# ProPrj___2025-02-25.net
KiCad netlist of a schematic drawn in EasyEDA Pro
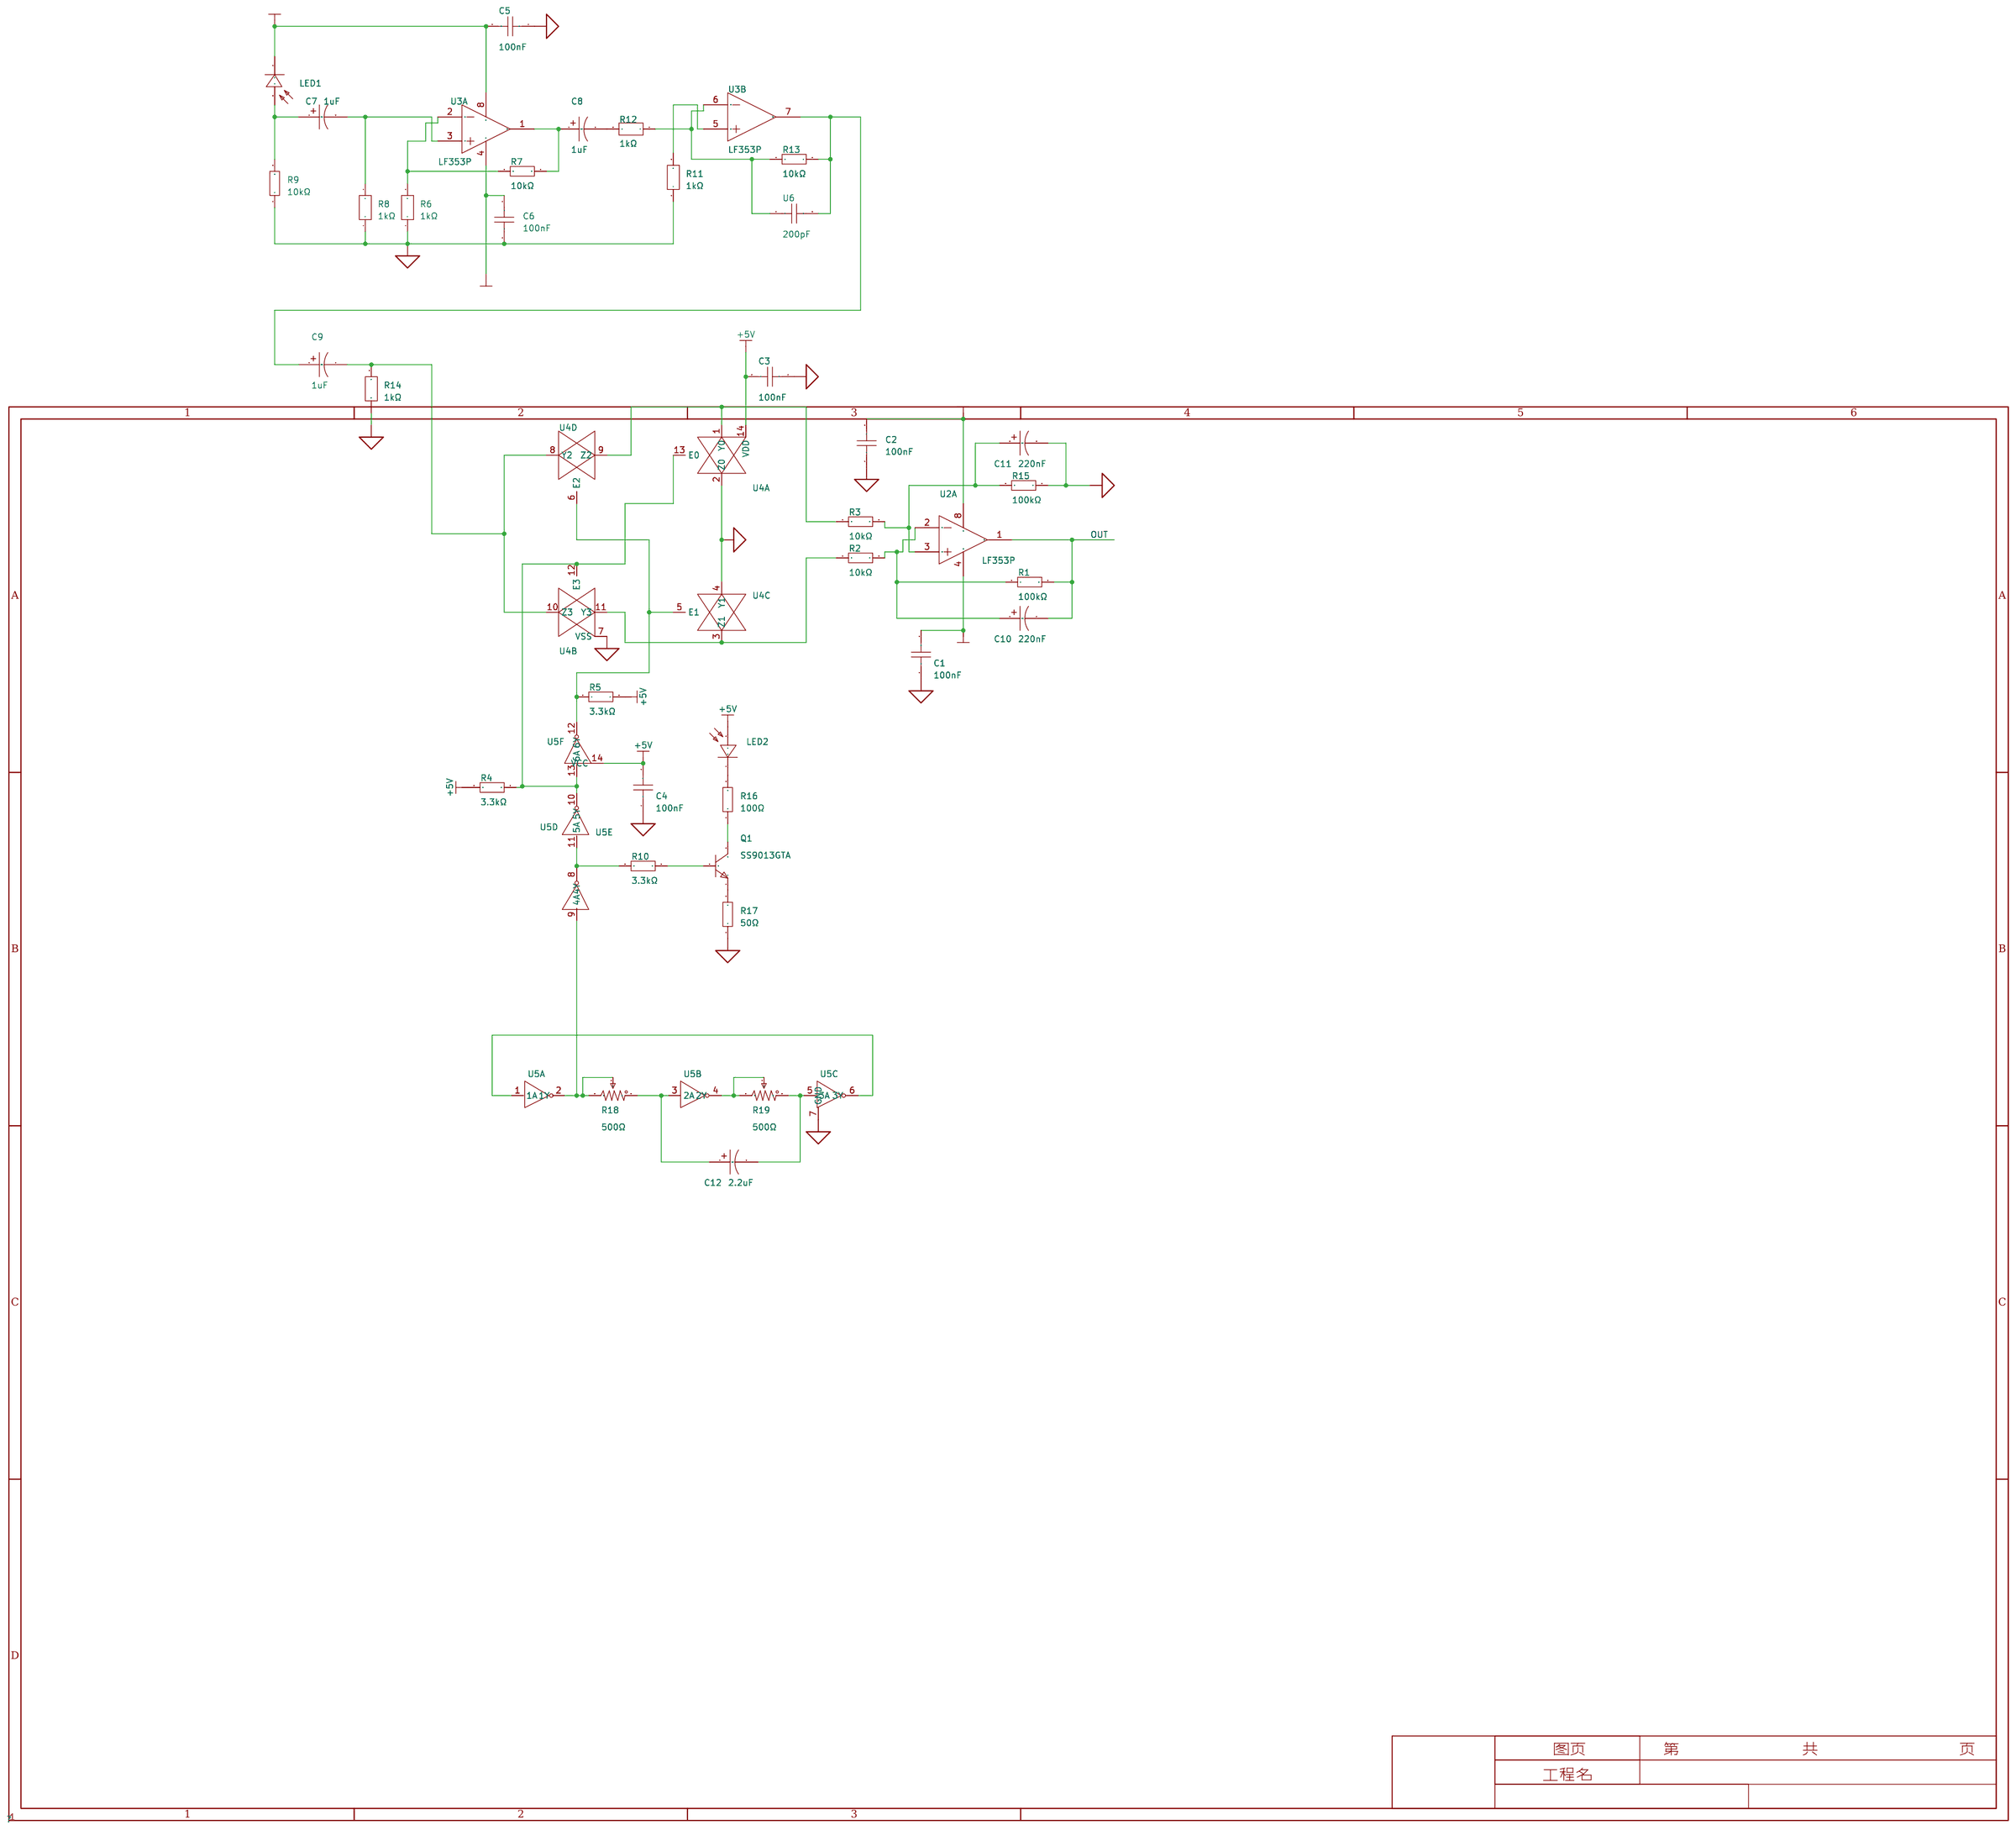
[diagram p0: schematic sheet]

(export (version "E")
  (design (tool "Eeschema 10.0.6"))
  (components
    (comp (ref "C1")
      (value "100nF")
      (footprint "easyedapro:C0402")
      (description "容值:100nF;精度:±10%;额定电压:50V;材质(温度系数):X7R;")
      (fields
        (field (name "Manufacturer Part") "GRM155R71H104KE14D")
        (field (name "Manufacturer") "muRata(村田)")
      )
      (libsource (lib "easyedapro") (part "GRM155R71H104KE14D"))
    )
    (comp (ref "C2")
      (value "100nF")
      (footprint "easyedapro:C0402")
      (description "容值:100nF;精度:±10%;额定电压:50V;材质(温度系数):X7R;")
      (fields
        (field (name "Manufacturer Part") "GRM155R71H104KE14D")
        (field (name "Manufacturer") "muRata(村田)")
      )
      (libsource (lib "easyedapro") (part "GRM155R71H104KE14D"))
    )
    (comp (ref "C3")
      (value "100nF")
      (footprint "easyedapro:C0402")
      (description "容值:100nF;精度:±10%;额定电压:50V;材质(温度系数):X7R;")
      (fields
        (field (name "Manufacturer Part") "GRM155R71H104KE14D")
        (field (name "Manufacturer") "muRata(村田)")
      )
      (libsource (lib "easyedapro") (part "GRM155R71H104KE14D"))
    )
    (comp (ref "C4")
      (value "100nF")
      (footprint "easyedapro:C0402")
      (description "容值:100nF;精度:±10%;额定电压:50V;材质(温度系数):X7R;")
      (fields
        (field (name "Manufacturer Part") "GRM155R71H104KE14D")
        (field (name "Manufacturer") "muRata(村田)")
      )
      (libsource (lib "easyedapro") (part "GRM155R71H104KE14D"))
    )
    (comp (ref "C5")
      (value "100nF")
      (footprint "easyedapro:C0402")
      (description "容值:100nF;精度:±10%;额定电压:50V;材质(温度系数):X7R;")
      (fields
        (field (name "Manufacturer Part") "GRM155R71H104KE14D")
        (field (name "Manufacturer") "muRata(村田)")
      )
      (libsource (lib "easyedapro") (part "GRM155R71H104KE14D"))
    )
    (comp (ref "C6")
      (value "100nF")
      (footprint "easyedapro:C0402")
      (description "容值:100nF;精度:±10%;额定电压:50V;材质(温度系数):X7R;")
      (fields
        (field (name "Manufacturer Part") "GRM155R71H104KE14D")
        (field (name "Manufacturer") "muRata(村田)")
      )
      (libsource (lib "easyedapro") (part "GRM155R71H104KE14D"))
    )
    (comp (ref "C7")
      (value "1uF")
      (footprint "easyedapro:CAP-TH_BD5.0-P2.00-D0.5-FD-1")
      (description "容值:1uF;精度:±20%;额定电压:50V;纹波电流:-;等效串联电阻:-;")
      (fields
        (field (name "Manufacturer Part") "50YXF1MEFC5X11")
        (field (name "Manufacturer") "rubycon(红宝石)")
      )
      (libsource (lib "easyedapro") (part "50YXF1MEFC5X11_C2927584"))
    )
    (comp (ref "C8")
      (value "1uF")
      (footprint "easyedapro:CAP-TH_BD5.0-P2.00-D0.5-FD-1")
      (description "容值:1uF;精度:±20%;额定电压:50V;纹波电流:-;等效串联电阻:-;")
      (fields
        (field (name "Manufacturer Part") "50YXF1MEFC5X11")
        (field (name "Manufacturer") "rubycon(红宝石)")
      )
      (libsource (lib "easyedapro") (part "50YXF1MEFC5X11_C2927584"))
    )
    (comp (ref "C9")
      (value "1uF")
      (footprint "easyedapro:CAP-TH_BD5.0-P2.00-D0.5-FD-1")
      (description "容值:1uF;精度:±20%;额定电压:50V;纹波电流:-;等效串联电阻:-;")
      (fields
        (field (name "Manufacturer Part") "50YXF1MEFC5X11")
        (field (name "Manufacturer") "rubycon(红宝石)")
      )
      (libsource (lib "easyedapro") (part "50YXF1MEFC5X11_C2927584"))
    )
    (comp (ref "C10")
      (value "220nF")
      (footprint "easyedapro:CAP-TH_BD5.0-P2.00-D0.5-FD-1")
      (description "容值:1uF;精度:±20%;额定电压:50V;纹波电流:-;等效串联电阻:-;")
      (fields
        (field (name "Manufacturer Part") "50YXF1MEFC5X11")
        (field (name "Manufacturer") "rubycon(红宝石)")
      )
      (libsource (lib "easyedapro") (part "50YXF1MEFC5X11_C2927584"))
    )
    (comp (ref "C11")
      (value "220nF")
      (footprint "easyedapro:CAP-TH_BD5.0-P2.00-D0.5-FD-1")
      (description "容值:1uF;精度:±20%;额定电压:50V;纹波电流:-;等效串联电阻:-;")
      (fields
        (field (name "Manufacturer Part") "50YXF1MEFC5X11")
        (field (name "Manufacturer") "rubycon(红宝石)")
      )
      (libsource (lib "easyedapro") (part "50YXF1MEFC5X11_C2927584"))
    )
    (comp (ref "C12")
      (value "2.2uF")
      (footprint "easyedapro:CAP-TH_BD5.0-P2.00-D0.5-FD-1")
      (description "容值:1uF;精度:±20%;额定电压:50V;纹波电流:-;等效串联电阻:-;")
      (fields
        (field (name "Manufacturer Part") "50YXF1MEFC5X11")
        (field (name "Manufacturer") "rubycon(红宝石)")
      )
      (libsource (lib "easyedapro") (part "50YXF1MEFC5X11_C2927584"))
    )
    (comp (ref "LED1")
      (value "MHL560PD03BRT")
      (footprint "easyedapro:LED-TH_BD4.2-P2.54-RD")
      (description "反向电压:30V;接收角:-;峰值波长:940nm;频谱范围:-;暗电流:5nA;")
      (fields (field (name "Manufacturer") "MEIHUA(美华)"))
      (libsource (lib "easyedapro") (part "MHL560PD03BRT"))
    )
    (comp (ref "LED2")
      (value "MHL560PD03BRT")
      (footprint "easyedapro:LED-TH_BD4.2-P2.54-RD")
      (description "反向电压:30V;接收角:-;峰值波长:940nm;频谱范围:-;暗电流:5nA;")
      (fields (field (name "Manufacturer") "MEIHUA(美华)"))
      (libsource (lib "easyedapro") (part "MHL560PD03BRT"))
    )
    (comp (ref "Q1")
      (value "SS9013GTA")
      (footprint "easyedapro:TO-92-3_L4.8-W3.7-P1.27-L")
      (description "晶体管类型:NPN;集电极电流(Ic):500mA;集射极击穿电压(Vceo):20V;功率(Pd):625mW;直流电流增益(hFE@Ic,Vce):112@50mA,1V;")
      (fields (field (name "Manufacturer") "onsemi(安森美)"))
      (libsource (lib "easyedapro") (part "SS9013GTA"))
    )
    (comp (ref "R1")
      (value "100kΩ")
      (footprint "easyedapro:R0402")
      (description "电阻类型:厚膜电阻;阻值:100kΩ;精度:±1%;功率:62.5mW;最大工作电压:50V;温度系数:±100ppm/°C;")
      (fields (field (name "Manufacturer Part") "RC0402FR-07100KL") (field (name "Manufacturer") "YAGEO(国巨)"))
      (libsource (lib "easyedapro") (part "RC0402FR-07100KL"))
    )
    (comp (ref "R2")
      (value "10kΩ")
      (footprint "easyedapro:R0402")
      (description "电阻类型:厚膜电阻;阻值:10kΩ;精度:±1%;功率:62.5mW;最大工作电压:50V;温度系数:±100ppm/°C;")
      (fields (field (name "Manufacturer Part") "RC0402FR-0710KL") (field (name "Manufacturer") "YAGEO(国巨)"))
      (libsource (lib "easyedapro") (part "RC0402FR-0710KL"))
    )
    (comp (ref "R3")
      (value "10kΩ")
      (footprint "easyedapro:R0402")
      (description "电阻类型:厚膜电阻;阻值:10kΩ;精度:±1%;功率:62.5mW;最大工作电压:50V;温度系数:±100ppm/°C;")
      (fields (field (name "Manufacturer Part") "RC0402FR-0710KL") (field (name "Manufacturer") "YAGEO(国巨)"))
      (libsource (lib "easyedapro") (part "RC0402FR-0710KL"))
    )
    (comp (ref "R4")
      (value "3.3kΩ")
      (footprint "easyedapro:R0402")
      (description "电阻类型:厚膜电阻;阻值:3.3kΩ;精度:±1%;功率:62.5mW;最大工作电压:50V;温度系数:±100ppm/°C;")
      (fields (field (name "Manufacturer Part") "RC0402FR-073K3L") (field (name "Manufacturer") "YAGEO(国巨)"))
      (libsource (lib "easyedapro") (part "RC0402FR-073K3L"))
    )
    (comp (ref "R5")
      (value "3.3kΩ")
      (footprint "easyedapro:R0402")
      (description "电阻类型:厚膜电阻;阻值:3.3kΩ;精度:±1%;功率:62.5mW;最大工作电压:50V;温度系数:±100ppm/°C;")
      (fields (field (name "Manufacturer Part") "RC0402FR-073K3L") (field (name "Manufacturer") "YAGEO(国巨)"))
      (libsource (lib "easyedapro") (part "RC0402FR-073K3L"))
    )
    (comp (ref "R6")
      (value "1kΩ")
      (footprint "easyedapro:R0402")
      (description "电阻类型:薄膜电阻;阻值:1kΩ;精度:±0.1%;功率:62.5mW;最大工作电压:50V;温度系数:±25ppm/°C;")
      (fields (field (name "Manufacturer Part") "RT0402BRD071KL") (field (name "Manufacturer") "YAGEO(国巨)"))
      (libsource (lib "easyedapro") (part "RT0402BRD071KL"))
    )
    (comp (ref "R7")
      (value "10kΩ")
      (footprint "easyedapro:R0402")
      (description "电阻类型:厚膜电阻;阻值:10kΩ;精度:±1%;功率:62.5mW;最大工作电压:50V;温度系数:±100ppm/°C;")
      (fields (field (name "Manufacturer Part") "RC0402FR-0710KL") (field (name "Manufacturer") "YAGEO(国巨)"))
      (libsource (lib "easyedapro") (part "RC0402FR-0710KL"))
    )
    (comp (ref "R8")
      (value "1kΩ")
      (footprint "easyedapro:R0402")
      (description "电阻类型:薄膜电阻;阻值:1kΩ;精度:±0.1%;功率:62.5mW;最大工作电压:50V;温度系数:±25ppm/°C;")
      (fields (field (name "Manufacturer Part") "RT0402BRD071KL") (field (name "Manufacturer") "YAGEO(国巨)"))
      (libsource (lib "easyedapro") (part "RT0402BRD071KL"))
    )
    (comp (ref "R9")
      (value "10kΩ")
      (footprint "easyedapro:R0402")
      (description "电阻类型:厚膜电阻;阻值:10kΩ;精度:±1%;功率:62.5mW;最大工作电压:50V;温度系数:±100ppm/°C;")
      (fields (field (name "Manufacturer Part") "RC0402FR-0710KL") (field (name "Manufacturer") "YAGEO(国巨)"))
      (libsource (lib "easyedapro") (part "RC0402FR-0710KL"))
    )
    (comp (ref "R10")
      (value "3.3kΩ")
      (footprint "easyedapro:R0402")
      (description "电阻类型:厚膜电阻;阻值:3.3kΩ;精度:±1%;功率:62.5mW;最大工作电压:50V;温度系数:±100ppm/°C;")
      (fields (field (name "Manufacturer Part") "RC0402FR-073K3L") (field (name "Manufacturer") "YAGEO(国巨)"))
      (libsource (lib "easyedapro") (part "RC0402FR-073K3L"))
    )
    (comp (ref "R11")
      (value "1kΩ")
      (footprint "easyedapro:R0402")
      (description "电阻类型:薄膜电阻;阻值:1kΩ;精度:±0.1%;功率:62.5mW;最大工作电压:50V;温度系数:±25ppm/°C;")
      (fields (field (name "Manufacturer Part") "RT0402BRD071KL") (field (name "Manufacturer") "YAGEO(国巨)"))
      (libsource (lib "easyedapro") (part "RT0402BRD071KL"))
    )
    (comp (ref "R12")
      (value "1kΩ")
      (footprint "easyedapro:R0402")
      (description "电阻类型:薄膜电阻;阻值:1kΩ;精度:±0.1%;功率:62.5mW;最大工作电压:50V;温度系数:±25ppm/°C;")
      (fields (field (name "Manufacturer Part") "RT0402BRD071KL") (field (name "Manufacturer") "YAGEO(国巨)"))
      (libsource (lib "easyedapro") (part "RT0402BRD071KL"))
    )
    (comp (ref "R13")
      (value "10kΩ")
      (footprint "easyedapro:R0402")
      (description "电阻类型:厚膜电阻;阻值:10kΩ;精度:±1%;功率:62.5mW;最大工作电压:50V;温度系数:±100ppm/°C;")
      (fields (field (name "Manufacturer Part") "RC0402FR-0710KL") (field (name "Manufacturer") "YAGEO(国巨)"))
      (libsource (lib "easyedapro") (part "RC0402FR-0710KL"))
    )
    (comp (ref "R14")
      (value "1kΩ")
      (footprint "easyedapro:R0402")
      (description "电阻类型:薄膜电阻;阻值:1kΩ;精度:±0.1%;功率:62.5mW;最大工作电压:50V;温度系数:±25ppm/°C;")
      (fields (field (name "Manufacturer Part") "RT0402BRD071KL") (field (name "Manufacturer") "YAGEO(国巨)"))
      (libsource (lib "easyedapro") (part "RT0402BRD071KL"))
    )
    (comp (ref "R15")
      (value "100kΩ")
      (footprint "easyedapro:R0402")
      (description "电阻类型:厚膜电阻;阻值:100kΩ;精度:±1%;功率:62.5mW;最大工作电压:50V;温度系数:±100ppm/°C;")
      (fields (field (name "Manufacturer Part") "RC0402FR-07100KL") (field (name "Manufacturer") "YAGEO(国巨)"))
      (libsource (lib "easyedapro") (part "RC0402FR-07100KL"))
    )
    (comp (ref "R16")
      (value "100Ω")
      (footprint "easyedapro:R0402")
      (description "电阻类型:厚膜电阻;阻值:100Ω;精度:±1%;功率:62.5mW;最大工作电压:50V;温度系数:±200ppm/°C;")
      (fields
        (field (name "Manufacturer Part") "0402WGF1000TCE")
        (field (name "Manufacturer") "UNI-ROYAL(厚声)")
      )
      (libsource (lib "easyedapro") (part "0402WGF1000TCE"))
    )
    (comp (ref "R17")
      (value "50Ω")
      (footprint "easyedapro:R0402")
      (description "电阻类型:薄膜电阻;阻值:50Ω;精度:±0.1%;功率:62.5mW;温度系数:±50ppm/°C;")
      (fields (field (name "Manufacturer Part") "RT0402BRE0750RL") (field (name "Manufacturer") "YAGEO(国巨)"))
      (libsource (lib "easyedapro") (part "RT0402BRE0750RL"))
    )
    (comp (ref "R18")
      (value "500Ω")
      (footprint "easyedapro:RES-ADJ-TH_3P-L10.0-W10.0-P2.50-L")
      (description "阻值:10kΩ;精度:±10%;")
      (fields (field (name "Manufacturer Part") "3296W-1-103") (field (name "Manufacturer") "BOCHEN(博晨)"))
      (libsource (lib "easyedapro") (part "3296W-1-103"))
    )
    (comp (ref "R19")
      (value "500Ω")
      (footprint "easyedapro:RES-ADJ-TH_3P-L10.0-W10.0-P2.50-L")
      (description "阻值:10kΩ;精度:±10%;")
      (fields (field (name "Manufacturer Part") "3296W-1-103") (field (name "Manufacturer") "BOCHEN(博晨)"))
      (libsource (lib "easyedapro") (part "3296W-1-103"))
    )
    (comp (ref "U2")
      (value "LF353P")
      (footprint "easyedapro:DIP-8_L10.1-W6.3-P2.54-LS7.6-BL")
      (description "增益带宽积(GBP):3MHz;输入偏置电流(Ib):50pA;输入失调电压(Vos):5mV;压摆率(SR):13V/us;")
      (fields (field (name "Manufacturer") "TI(德州仪器)"))
      (libsource (lib "easyedapro") (part "LF353P"))
    )
    (comp (ref "U3")
      (value "LF353P")
      (footprint "easyedapro:DIP-8_L10.1-W6.3-P2.54-LS7.6-BL")
      (description "增益带宽积(GBP):3MHz;输入偏置电流(Ib):50pA;输入失调电压(Vos):5mV;压摆率(SR):13V/us;")
      (fields (field (name "Manufacturer") "TI(德州仪器)"))
      (libsource (lib "easyedapro") (part "LF353P"))
    )
    (comp (ref "U4")
      (value "CD4066BE")
      (footprint "easyedapro:DIP-14_L20.0-W7.6-P2.54-LS7.6-BL")
      (description "开关电路:单刀单掷(SPST);通道数:4;导通电阻(Ron@VCC):1.3kΩ;")
      (fields (field (name "Manufacturer") "HGSEMI(华冠)"))
      (libsource (lib "easyedapro") (part "CD4066BE_C507158"))
    )
    (comp (ref "U5")
      (value "SN74HC04N(XBLW)")
      (footprint "easyedapro:DIP-14_L19.6-W6.4-P2.54-LS7.6-BL")
      (description "输入类型:施密特触发器;电源电压:2V~6V;供电电流(最大值):2uA;电路数:6;最大传播延迟(tpd):7ns;")
      (fields (field (name "Manufacturer") "XBLW(芯伯乐)"))
      (libsource (lib "easyedapro") (part "SN74HC04N(XBLW)"))
    )
    (comp (ref "U6")
      (value "200pF")
      (footprint "easyedapro:C0402")
      (description "容值:200pF;精度:±5%;额定电压:50V;材质(温度系数):C0G;")
      (fields
        (field (name "Manufacturer Part") "GRM1555C1H201JA01D")
        (field (name "Manufacturer") "muRata(村田)")
      )
      (libsource (lib "easyedapro") (part "GRM1555C1H201JA01D"))
    )
  )
  (nets
    (net (code "1") (name "+5V") (class "Default")
      (node (ref "C3") (pin "2") (pinfunction "2_2") (pintype "unspecified"))
      (node (ref "C4") (pin "2") (pinfunction "2_2") (pintype "unspecified"))
      (node (ref "LED2") (pin "2") (pinfunction "A_2") (pintype "unspecified"))
      (node (ref "R4") (pin "2") (pinfunction "2_2") (pintype "input"))
      (node (ref "R5") (pin "2") (pinfunction "2_2") (pintype "input"))
      (node (ref "U4") (pin "14") (pinfunction "VDD_14") (pintype "unspecified"))
      (node (ref "U5") (pin "14") (pinfunction "VCC_14") (pintype "unspecified"))
    )
    (net (code "2") (name "+12V") (class "Default")
      (node (ref "C2") (pin "2") (pinfunction "2_2") (pintype "unspecified"))
      (node (ref "C5") (pin "2") (pinfunction "2_2") (pintype "unspecified"))
      (node (ref "LED1") (pin "1") (pinfunction "C_1") (pintype "unspecified"))
      (node (ref "U2") (pin "8") (pinfunction "VCC+_8") (pintype "unspecified"))
      (node (ref "U3") (pin "8") (pinfunction "VCC+_8") (pintype "unspecified"))
    )
    (net (code "3") (name "-12V") (class "Default")
      (node (ref "C1") (pin "2") (pinfunction "2_2") (pintype "unspecified"))
      (node (ref "C6") (pin "1") (pinfunction "1_1") (pintype "unspecified"))
      (node (ref "U2") (pin "4") (pinfunction "VCC-_4") (pintype "unspecified"))
      (node (ref "U3") (pin "4") (pinfunction "VCC-_4") (pintype "unspecified"))
    )
    (net (code "4") (name "/OUT") (class "Default")
      (node (ref "C10") (pin "2") (pinfunction "2_2") (pintype "unspecified"))
      (node (ref "R1") (pin "2") (pinfunction "2_2") (pintype "input"))
      (node (ref "U2") (pin "1") (pinfunction "1OUT_1") (pintype "output"))
    )
    (net (code "5") (name "AGND") (class "Default")
      (node (ref "C1") (pin "1") (pinfunction "1_1") (pintype "unspecified"))
      (node (ref "C11") (pin "2") (pinfunction "2_2") (pintype "unspecified"))
      (node (ref "C2") (pin "1") (pinfunction "1_1") (pintype "unspecified"))
      (node (ref "C3") (pin "1") (pinfunction "1_1") (pintype "unspecified"))
      (node (ref "C4") (pin "1") (pinfunction "1_1") (pintype "unspecified"))
      (node (ref "C5") (pin "1") (pinfunction "1_1") (pintype "unspecified"))
      (node (ref "C6") (pin "2") (pinfunction "2_2") (pintype "unspecified"))
      (node (ref "R11") (pin "1") (pinfunction "1_1") (pintype "unspecified"))
      (node (ref "R14") (pin "1") (pinfunction "1_1") (pintype "unspecified"))
      (node (ref "R15") (pin "2") (pinfunction "2_2") (pintype "input"))
      (node (ref "R17") (pin "1") (pinfunction "1_1") (pintype "unspecified"))
      (node (ref "R6") (pin "1") (pinfunction "1_1") (pintype "unspecified"))
      (node (ref "R8") (pin "1") (pinfunction "1_1") (pintype "unspecified"))
      (node (ref "R9") (pin "1") (pinfunction "1_1") (pintype "input"))
      (node (ref "U4") (pin "2") (pinfunction "Z0_2") (pintype "unspecified"))
      (node (ref "U4") (pin "4") (pinfunction "Y1_4") (pintype "unspecified"))
      (node (ref "U4") (pin "7") (pinfunction "VSS_7") (pintype "unspecified"))
      (node (ref "U5") (pin "7") (pinfunction "GND_7") (pintype "unspecified"))
    )
    (net (code "6") (name "Net-(C8-Pad2)") (class "Default")
      (node (ref "C8") (pin "2") (pinfunction "2_2") (pintype "unspecified"))
      (node (ref "R12") (pin "2") (pinfunction "2_2") (pintype "unspecified"))
    )
    (net (code "7") (name "Net-(LED1-A)") (class "Default")
      (node (ref "C7") (pin "1") (pinfunction "1_1") (pintype "unspecified"))
      (node (ref "LED1") (pin "2") (pinfunction "A_2") (pintype "unspecified"))
      (node (ref "R9") (pin "2") (pinfunction "2_2") (pintype "input"))
    )
    (net (code "8") (name "Net-(LED2-C)") (class "Default")
      (node (ref "LED2") (pin "1") (pinfunction "C_1") (pintype "unspecified"))
      (node (ref "R16") (pin "2") (pinfunction "2_2") (pintype "input"))
    )
    (net (code "9") (name "Net-(Q1-B)") (class "Default")
      (node (ref "Q1") (pin "2") (pinfunction "B_2") (pintype "input"))
      (node (ref "R10") (pin "1") (pinfunction "1_1") (pintype "input"))
    )
    (net (code "10") (name "Net-(Q1-C)") (class "Default")
      (node (ref "Q1") (pin "3") (pinfunction "C_3") (pintype "input"))
      (node (ref "R16") (pin "1") (pinfunction "1_1") (pintype "input"))
    )
    (net (code "11") (name "Net-(Q1-E)") (class "Default")
      (node (ref "Q1") (pin "1") (pinfunction "E_1") (pintype "input"))
      (node (ref "R17") (pin "2") (pinfunction "2_2") (pintype "unspecified"))
    )
    (net (code "12") (name "Net-(U2A-1IN+)") (class "Default")
      (node (ref "C11") (pin "1") (pinfunction "1_1") (pintype "unspecified"))
      (node (ref "R15") (pin "1") (pinfunction "1_1") (pintype "input"))
      (node (ref "R3") (pin "2") (pinfunction "2_2") (pintype "input"))
      (node (ref "U2") (pin "3") (pinfunction "1IN+_3") (pintype "unspecified"))
    )
    (net (code "13") (name "Net-(U2A-1IN-)") (class "Default")
      (node (ref "C10") (pin "1") (pinfunction "1_1") (pintype "unspecified"))
      (node (ref "R1") (pin "1") (pinfunction "1_1") (pintype "input"))
      (node (ref "R2") (pin "2") (pinfunction "2_2") (pintype "input"))
      (node (ref "U2") (pin "2") (pinfunction "1IN-_2") (pintype "unspecified"))
    )
    (net (code "14") (name "Net-(U3A-1IN+)") (class "Default")
      (node (ref "C7") (pin "2") (pinfunction "2_2") (pintype "unspecified"))
      (node (ref "R8") (pin "2") (pinfunction "2_2") (pintype "unspecified"))
      (node (ref "U3") (pin "3") (pinfunction "1IN+_3") (pintype "unspecified"))
    )
    (net (code "15") (name "Net-(U3A-1IN-)") (class "Default")
      (node (ref "R6") (pin "2") (pinfunction "2_2") (pintype "unspecified"))
      (node (ref "R7") (pin "1") (pinfunction "1_1") (pintype "input"))
      (node (ref "U3") (pin "2") (pinfunction "1IN-_2") (pintype "unspecified"))
    )
    (net (code "16") (name "Net-(U3A-1OUT)") (class "Default")
      (node (ref "C8") (pin "1") (pinfunction "1_1") (pintype "unspecified"))
      (node (ref "R7") (pin "2") (pinfunction "2_2") (pintype "input"))
      (node (ref "U3") (pin "1") (pinfunction "1OUT_1") (pintype "output"))
    )
    (net (code "17") (name "Net-(U3B-2IN+)") (class "Default")
      (node (ref "R11") (pin "2") (pinfunction "2_2") (pintype "unspecified"))
      (node (ref "U3") (pin "5") (pinfunction "2IN+_5") (pintype "unspecified"))
    )
    (net (code "18") (name "Net-(U3B-2IN-)") (class "Default")
      (node (ref "R12") (pin "1") (pinfunction "1_1") (pintype "unspecified"))
      (node (ref "R13") (pin "1") (pinfunction "1_1") (pintype "input"))
      (node (ref "U3") (pin "6") (pinfunction "2IN-_6") (pintype "unspecified"))
      (node (ref "U6") (pin "1") (pinfunction "1_1") (pintype "unspecified"))
    )
    (net (code "19") (name "Net-(U3B-2OUT)") (class "Default")
      (node (ref "C9") (pin "1") (pinfunction "1_1") (pintype "unspecified"))
      (node (ref "R13") (pin "2") (pinfunction "2_2") (pintype "input"))
      (node (ref "U3") (pin "7") (pinfunction "2OUT_7") (pintype "output"))
      (node (ref "U6") (pin "2") (pinfunction "2_2") (pintype "unspecified"))
    )
    (net (code "20") (name "Net-(U4A-E0)") (class "Default")
      (node (ref "R4") (pin "1") (pinfunction "1_1") (pintype "input"))
      (node (ref "U4") (pin "12") (pinfunction "E3_12") (pintype "unspecified"))
      (node (ref "U4") (pin "13") (pinfunction "E0_13") (pintype "unspecified"))
      (node (ref "U5") (pin "10") (pinfunction "5Y_10") (pintype "unspecified"))
      (node (ref "U5") (pin "13") (pinfunction "6A_13") (pintype "unspecified"))
    )
    (net (code "21") (name "Net-(U4A-Y0)") (class "Default")
      (node (ref "R3") (pin "1") (pinfunction "1_1") (pintype "input"))
      (node (ref "U4") (pin "1") (pinfunction "Y0_1") (pintype "unspecified"))
      (node (ref "U4") (pin "9") (pinfunction "Z2_9") (pintype "unspecified"))
    )
    (net (code "22") (name "Net-(U4B-Y3)") (class "Default")
      (node (ref "R2") (pin "1") (pinfunction "1_1") (pintype "input"))
      (node (ref "U4") (pin "11") (pinfunction "Y3_11") (pintype "unspecified"))
      (node (ref "U4") (pin "3") (pinfunction "Z1_3") (pintype "unspecified"))
    )
    (net (code "23") (name "Net-(U4B-Z3)") (class "Default")
      (node (ref "C9") (pin "2") (pinfunction "2_2") (pintype "unspecified"))
      (node (ref "R14") (pin "2") (pinfunction "2_2") (pintype "unspecified"))
      (node (ref "U4") (pin "10") (pinfunction "Z3_10") (pintype "unspecified"))
      (node (ref "U4") (pin "8") (pinfunction "Y2_8") (pintype "unspecified"))
    )
    (net (code "24") (name "Net-(U4C-E1)") (class "Default")
      (node (ref "R5") (pin "1") (pinfunction "1_1") (pintype "input"))
      (node (ref "U4") (pin "5") (pinfunction "E1_5") (pintype "unspecified"))
      (node (ref "U4") (pin "6") (pinfunction "E2_6") (pintype "unspecified"))
      (node (ref "U5") (pin "12") (pinfunction "6Y_12") (pintype "unspecified"))
    )
    (net (code "25") (name "Net-(U5A-1A)") (class "Default")
      (node (ref "U5") (pin "1") (pinfunction "1A_1") (pintype "unspecified"))
      (node (ref "U5") (pin "6") (pinfunction "3Y_6") (pintype "unspecified"))
    )
    (net (code "26") (name "Net-(U5A-1Y)") (class "Default")
      (node (ref "R18") (pin "2") (pinfunction "2_2") (pintype "unspecified"))
      (node (ref "R18") (pin "3") (pinfunction "3_3") (pintype "unspecified"))
      (node (ref "U5") (pin "2") (pinfunction "1Y_2") (pintype "unspecified"))
      (node (ref "U5") (pin "9") (pinfunction "4A_9") (pintype "unspecified"))
    )
    (net (code "27") (name "Net-(U5B-2A)") (class "Default")
      (node (ref "C12") (pin "1") (pinfunction "1_1") (pintype "unspecified"))
      (node (ref "R18") (pin "1") (pinfunction "1_1") (pintype "unspecified"))
      (node (ref "U5") (pin "3") (pinfunction "2A_3") (pintype "unspecified"))
    )
    (net (code "28") (name "Net-(U5B-2Y)") (class "Default")
      (node (ref "R19") (pin "2") (pinfunction "2_2") (pintype "unspecified"))
      (node (ref "R19") (pin "3") (pinfunction "3_3") (pintype "unspecified"))
      (node (ref "U5") (pin "4") (pinfunction "2Y_4") (pintype "unspecified"))
    )
    (net (code "29") (name "Net-(U5C-3A)") (class "Default")
      (node (ref "C12") (pin "2") (pinfunction "2_2") (pintype "unspecified"))
      (node (ref "R19") (pin "1") (pinfunction "1_1") (pintype "unspecified"))
      (node (ref "U5") (pin "5") (pinfunction "3A_5") (pintype "unspecified"))
    )
    (net (code "30") (name "Net-(U5D-4Y)") (class "Default")
      (node (ref "R10") (pin "2") (pinfunction "2_2") (pintype "input"))
      (node (ref "U5") (pin "11") (pinfunction "5A_11") (pintype "unspecified"))
      (node (ref "U5") (pin "8") (pinfunction "4Y_8") (pintype "unspecified"))
    )
  )
)
